# PCB-TLY-JACK-INTFC.net
KiCad netlist of a schematic drawn in EAGLE
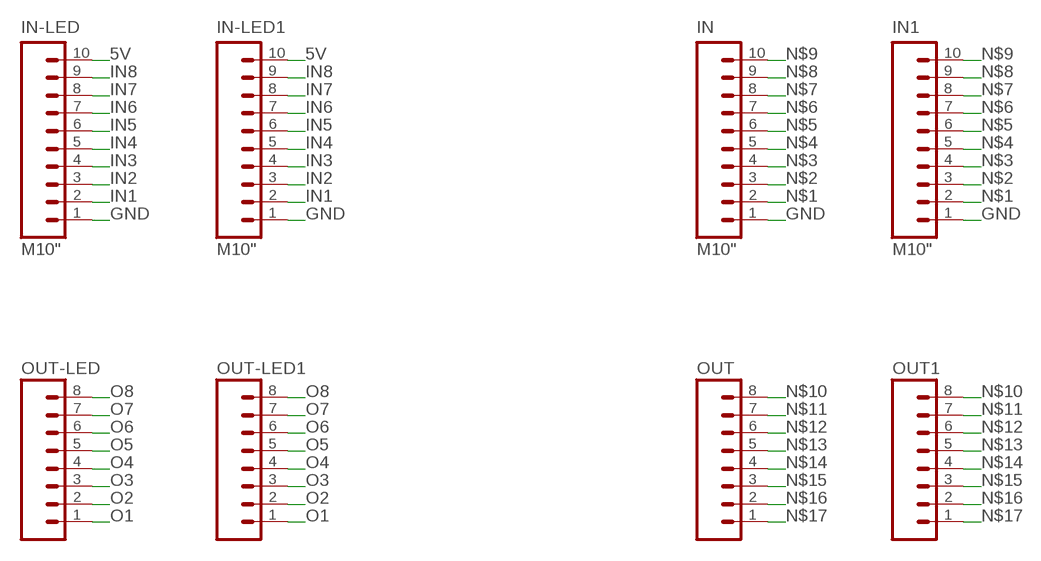
[diagram p0: schematic, sheet 1]

(export (version "E")
  (design (tool "Eeschema 10.0.6"))
  (components
    (comp (ref "IN")
      (value "M10\"")
      (footprint "eagle-import:1X10")
      (libsource (lib "eagle-import") (part "M10{dblquote}"))
    )
    (comp (ref "IN-LED")
      (value "M10\"")
      (footprint "eagle-import:1X10")
      (libsource (lib "eagle-import") (part "M10{dblquote}"))
    )
    (comp (ref "IN-LED1")
      (value "M10\"")
      (footprint "eagle-import:1X10")
      (libsource (lib "eagle-import") (part "M10{dblquote}"))
    )
    (comp (ref "IN1")
      (value "M10\"")
      (footprint "eagle-import:1X10")
      (libsource (lib "eagle-import") (part "M10{dblquote}"))
    )
    (comp (ref "OUT")
      (value "M081X08")
      (footprint "eagle-import:1X08")
      (libsource (lib "eagle-import") (part "M081X08"))
    )
    (comp (ref "OUT-LED")
      (value "M081X08")
      (footprint "eagle-import:1X08")
      (libsource (lib "eagle-import") (part "M081X08"))
    )
    (comp (ref "OUT-LED1")
      (value "M081X08")
      (footprint "eagle-import:1X08")
      (libsource (lib "eagle-import") (part "M081X08"))
    )
    (comp (ref "OUT1")
      (value "M081X08")
      (footprint "eagle-import:1X08")
      (libsource (lib "eagle-import") (part "M081X08"))
    )
  )
  (nets
    (net (code "1") (name "/5V") (class "Default")
      (node (ref "IN-LED") (pin "10") (pinfunction "10_10") (pintype "passive"))
      (node (ref "IN-LED1") (pin "10") (pinfunction "10_10") (pintype "passive"))
    )
    (net (code "2") (name "/GND") (class "Default")
      (node (ref "IN") (pin "1") (pinfunction "1_1") (pintype "passive"))
      (node (ref "IN-LED") (pin "1") (pinfunction "1_1") (pintype "passive"))
      (node (ref "IN-LED1") (pin "1") (pinfunction "1_1") (pintype "passive"))
      (node (ref "IN1") (pin "1") (pinfunction "1_1") (pintype "passive"))
    )
    (net (code "3") (name "/IN1") (class "Default")
      (node (ref "IN-LED") (pin "2") (pinfunction "2_2") (pintype "passive"))
      (node (ref "IN-LED1") (pin "2") (pinfunction "2_2") (pintype "passive"))
    )
    (net (code "4") (name "/IN2") (class "Default")
      (node (ref "IN-LED") (pin "3") (pinfunction "3_3") (pintype "passive"))
      (node (ref "IN-LED1") (pin "3") (pinfunction "3_3") (pintype "passive"))
    )
    (net (code "5") (name "/IN3") (class "Default")
      (node (ref "IN-LED") (pin "4") (pinfunction "4_4") (pintype "passive"))
      (node (ref "IN-LED1") (pin "4") (pinfunction "4_4") (pintype "passive"))
    )
    (net (code "6") (name "/IN4") (class "Default")
      (node (ref "IN-LED") (pin "5") (pinfunction "5_5") (pintype "passive"))
      (node (ref "IN-LED1") (pin "5") (pinfunction "5_5") (pintype "passive"))
    )
    (net (code "7") (name "/IN5") (class "Default")
      (node (ref "IN-LED") (pin "6") (pinfunction "6_6") (pintype "passive"))
      (node (ref "IN-LED1") (pin "6") (pinfunction "6_6") (pintype "passive"))
    )
    (net (code "8") (name "/IN6") (class "Default")
      (node (ref "IN-LED") (pin "7") (pinfunction "7_7") (pintype "passive"))
      (node (ref "IN-LED1") (pin "7") (pinfunction "7_7") (pintype "passive"))
    )
    (net (code "9") (name "/IN7") (class "Default")
      (node (ref "IN-LED") (pin "8") (pinfunction "8_8") (pintype "passive"))
      (node (ref "IN-LED1") (pin "8") (pinfunction "8_8") (pintype "passive"))
    )
    (net (code "10") (name "/IN8") (class "Default")
      (node (ref "IN-LED") (pin "9") (pinfunction "9_9") (pintype "passive"))
      (node (ref "IN-LED1") (pin "9") (pinfunction "9_9") (pintype "passive"))
    )
    (net (code "11") (name "/N$1") (class "Default")
      (node (ref "IN") (pin "2") (pinfunction "2_2") (pintype "passive"))
      (node (ref "IN1") (pin "2") (pinfunction "2_2") (pintype "passive"))
    )
    (net (code "12") (name "/N$2") (class "Default")
      (node (ref "IN") (pin "3") (pinfunction "3_3") (pintype "passive"))
      (node (ref "IN1") (pin "3") (pinfunction "3_3") (pintype "passive"))
    )
    (net (code "13") (name "/N$3") (class "Default")
      (node (ref "IN") (pin "4") (pinfunction "4_4") (pintype "passive"))
      (node (ref "IN1") (pin "4") (pinfunction "4_4") (pintype "passive"))
    )
    (net (code "14") (name "/N$4") (class "Default")
      (node (ref "IN") (pin "5") (pinfunction "5_5") (pintype "passive"))
      (node (ref "IN1") (pin "5") (pinfunction "5_5") (pintype "passive"))
    )
    (net (code "15") (name "/N$5") (class "Default")
      (node (ref "IN") (pin "6") (pinfunction "6_6") (pintype "passive"))
      (node (ref "IN1") (pin "6") (pinfunction "6_6") (pintype "passive"))
    )
    (net (code "16") (name "/N$6") (class "Default")
      (node (ref "IN") (pin "7") (pinfunction "7_7") (pintype "passive"))
      (node (ref "IN1") (pin "7") (pinfunction "7_7") (pintype "passive"))
    )
    (net (code "17") (name "/N$7") (class "Default")
      (node (ref "IN") (pin "8") (pinfunction "8_8") (pintype "passive"))
      (node (ref "IN1") (pin "8") (pinfunction "8_8") (pintype "passive"))
    )
    (net (code "18") (name "/N$8") (class "Default")
      (node (ref "IN") (pin "9") (pinfunction "9_9") (pintype "passive"))
      (node (ref "IN1") (pin "9") (pinfunction "9_9") (pintype "passive"))
    )
    (net (code "19") (name "/N$9") (class "Default")
      (node (ref "IN") (pin "10") (pinfunction "10_10") (pintype "passive"))
      (node (ref "IN1") (pin "10") (pinfunction "10_10") (pintype "passive"))
    )
    (net (code "20") (name "/N$10") (class "Default")
      (node (ref "OUT") (pin "8") (pinfunction "8_8") (pintype "passive"))
      (node (ref "OUT1") (pin "8") (pinfunction "8_8") (pintype "passive"))
    )
    (net (code "21") (name "/N$11") (class "Default")
      (node (ref "OUT") (pin "7") (pinfunction "7_7") (pintype "passive"))
      (node (ref "OUT1") (pin "7") (pinfunction "7_7") (pintype "passive"))
    )
    (net (code "22") (name "/N$12") (class "Default")
      (node (ref "OUT") (pin "6") (pinfunction "6_6") (pintype "passive"))
      (node (ref "OUT1") (pin "6") (pinfunction "6_6") (pintype "passive"))
    )
    (net (code "23") (name "/N$13") (class "Default")
      (node (ref "OUT") (pin "5") (pinfunction "5_5") (pintype "passive"))
      (node (ref "OUT1") (pin "5") (pinfunction "5_5") (pintype "passive"))
    )
    (net (code "24") (name "/N$14") (class "Default")
      (node (ref "OUT") (pin "4") (pinfunction "4_4") (pintype "passive"))
      (node (ref "OUT1") (pin "4") (pinfunction "4_4") (pintype "passive"))
    )
    (net (code "25") (name "/N$15") (class "Default")
      (node (ref "OUT") (pin "3") (pinfunction "3_3") (pintype "passive"))
      (node (ref "OUT1") (pin "3") (pinfunction "3_3") (pintype "passive"))
    )
    (net (code "26") (name "/N$16") (class "Default")
      (node (ref "OUT") (pin "2") (pinfunction "2_2") (pintype "passive"))
      (node (ref "OUT1") (pin "2") (pinfunction "2_2") (pintype "passive"))
    )
    (net (code "27") (name "/N$17") (class "Default")
      (node (ref "OUT") (pin "1") (pinfunction "1_1") (pintype "passive"))
      (node (ref "OUT1") (pin "1") (pinfunction "1_1") (pintype "passive"))
    )
    (net (code "28") (name "/O1") (class "Default")
      (node (ref "OUT-LED") (pin "1") (pinfunction "1_1") (pintype "passive"))
      (node (ref "OUT-LED1") (pin "1") (pinfunction "1_1") (pintype "passive"))
    )
    (net (code "29") (name "/O2") (class "Default")
      (node (ref "OUT-LED") (pin "2") (pinfunction "2_2") (pintype "passive"))
      (node (ref "OUT-LED1") (pin "2") (pinfunction "2_2") (pintype "passive"))
    )
    (net (code "30") (name "/O3") (class "Default")
      (node (ref "OUT-LED") (pin "3") (pinfunction "3_3") (pintype "passive"))
      (node (ref "OUT-LED1") (pin "3") (pinfunction "3_3") (pintype "passive"))
    )
    (net (code "31") (name "/O4") (class "Default")
      (node (ref "OUT-LED") (pin "4") (pinfunction "4_4") (pintype "passive"))
      (node (ref "OUT-LED1") (pin "4") (pinfunction "4_4") (pintype "passive"))
    )
    (net (code "32") (name "/O5") (class "Default")
      (node (ref "OUT-LED") (pin "5") (pinfunction "5_5") (pintype "passive"))
      (node (ref "OUT-LED1") (pin "5") (pinfunction "5_5") (pintype "passive"))
    )
    (net (code "33") (name "/O6") (class "Default")
      (node (ref "OUT-LED") (pin "6") (pinfunction "6_6") (pintype "passive"))
      (node (ref "OUT-LED1") (pin "6") (pinfunction "6_6") (pintype "passive"))
    )
    (net (code "34") (name "/O7") (class "Default")
      (node (ref "OUT-LED") (pin "7") (pinfunction "7_7") (pintype "passive"))
      (node (ref "OUT-LED1") (pin "7") (pinfunction "7_7") (pintype "passive"))
    )
    (net (code "35") (name "/O8") (class "Default")
      (node (ref "OUT-LED") (pin "8") (pinfunction "8_8") (pintype "passive"))
      (node (ref "OUT-LED1") (pin "8") (pinfunction "8_8") (pintype "passive"))
    )
  )
)
